# Board1.net
KiCad netlist of a schematic drawn in EAGLE
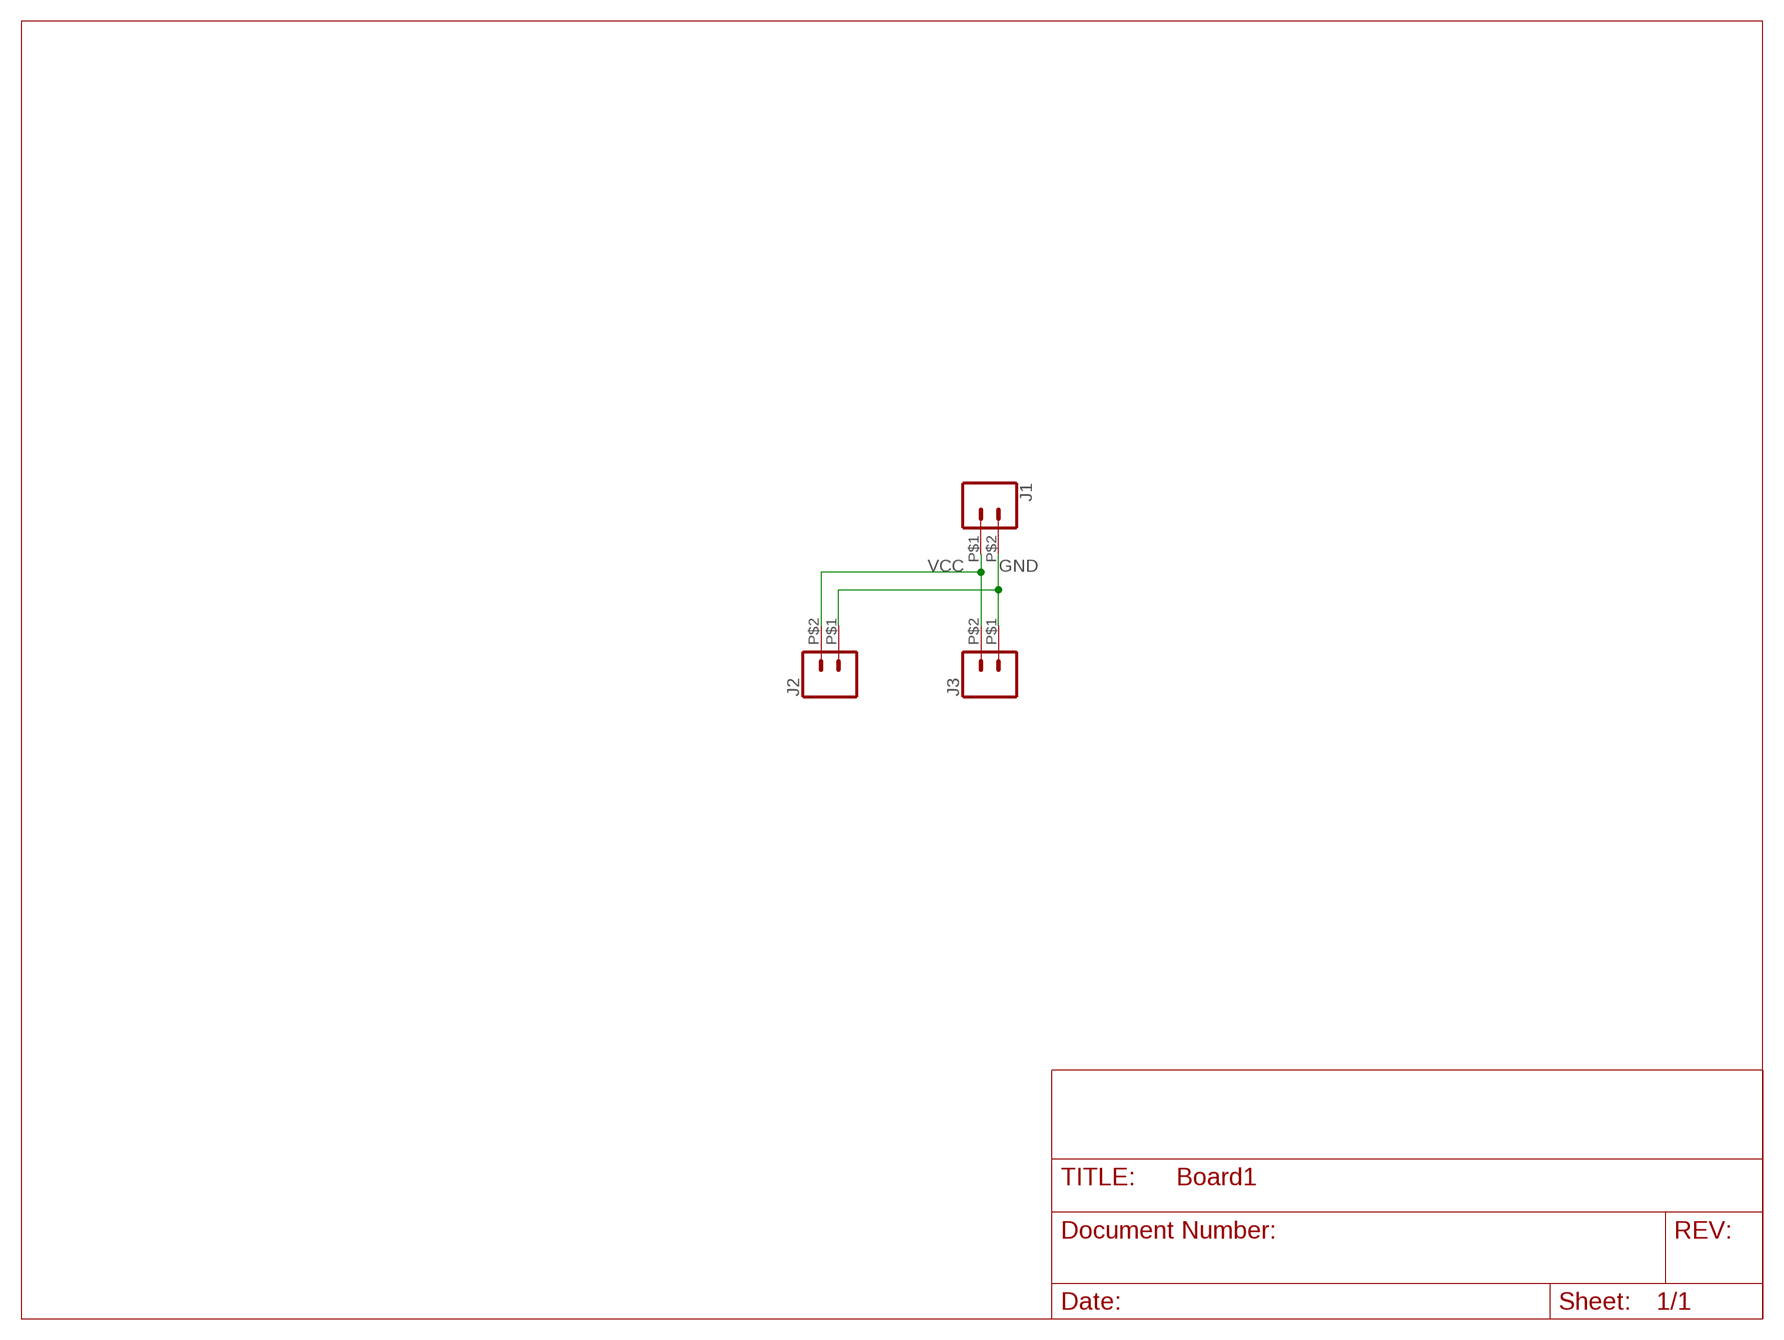
[diagram p0: schematic, sheet 1]

(export (version "E")
  (design (tool "Eeschema 10.0.6"))
  (components
    (comp (ref "J1")
      (value "CONN_02PTH2")
      (footprint "eagle-import:1X02_BIG")
      (libsource (lib "eagle-import") (part "CONN_02PTH2"))
    )
    (comp (ref "J2")
      (value "CONN_02PTH2")
      (footprint "eagle-import:1X02_BIG")
      (libsource (lib "eagle-import") (part "CONN_02PTH2"))
    )
    (comp (ref "J3")
      (value "CONN_02PTH2")
      (footprint "eagle-import:1X02_BIG")
      (libsource (lib "eagle-import") (part "CONN_02PTH2"))
    )
  )
  (nets
    (net (code "1") (name "/GND") (class "Default")
      (node (ref "J1") (pin "P$2") (pinfunction "2_P$2") (pintype "passive"))
      (node (ref "J2") (pin "P$1") (pinfunction "1_P$1") (pintype "passive"))
      (node (ref "J3") (pin "P$1") (pinfunction "1_P$1") (pintype "passive"))
    )
    (net (code "2") (name "/VCC") (class "Default")
      (node (ref "J1") (pin "P$1") (pinfunction "1_P$1") (pintype "passive"))
      (node (ref "J2") (pin "P$2") (pinfunction "2_P$2") (pintype "passive"))
      (node (ref "J3") (pin "P$2") (pinfunction "2_P$2") (pintype "passive"))
    )
  )
)
